# icarus-rev01.net
KiCad netlist of a schematic drawn in EAGLE
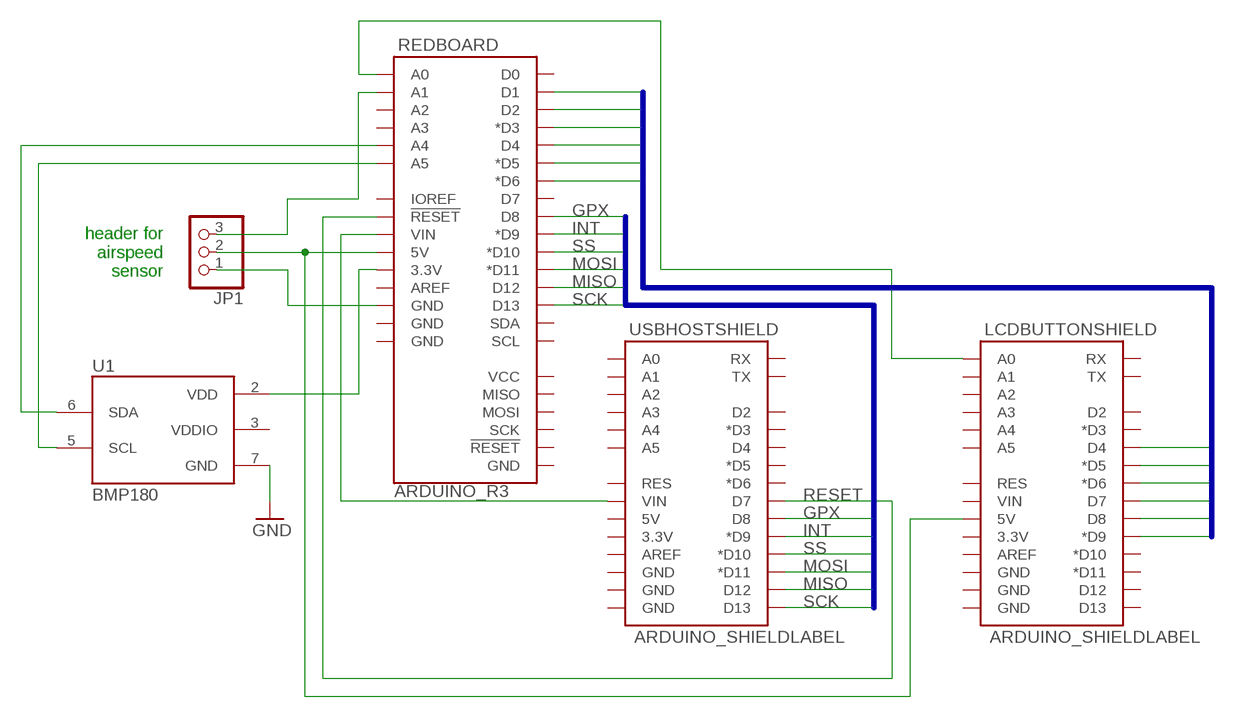
[diagram p0: schematic, sheet 1]

(export (version "E")
  (design (tool "Eeschema 10.0.6"))
  (components
    (comp (ref "JP1")
      (value "PINHD-1X3/90")
      (footprint "eagle-import:1X03_90")
      (libsource (lib "eagle-import") (part "PINHD-1X3/90"))
    )
    (comp (ref "LCDBUTTONSHIELD")
      (value "ARDUINO_SHIELDLABEL")
      (footprint "eagle-import:DUEMILANOVE_SHIELD")
      (libsource (lib "eagle-import") (part "ARDUINO_SHIELDLABEL"))
    )
    (comp (ref "REDBOARD")
      (value "ARDUINO_R3")
      (footprint "eagle-import:ARDUINO_R3")
      (libsource (lib "eagle-import") (part "ARDUINO_R3"))
    )
    (comp (ref "U1")
      (value "BMP180")
      (footprint "eagle-import:BMP180")
      (libsource (lib "eagle-import") (part "BMP180"))
    )
    (comp (ref "USBHOSTSHIELD")
      (value "ARDUINO_SHIELDLABEL")
      (footprint "eagle-import:DUEMILANOVE_SHIELD")
      (libsource (lib "eagle-import") (part "ARDUINO_SHIELDLABEL"))
    )
  )
  (nets
    (net (code "1") (name "/D0") (class "Default")
      (node (ref "LCDBUTTONSHIELD") (pin "D4") (pinfunction "D4_D4") (pintype "bidirectional"))
      (node (ref "REDBOARD") (pin "D4") (pinfunction "D4_D4") (pintype "bidirectional"))
    )
    (net (code "2") (name "/D1") (class "Default")
      (node (ref "LCDBUTTONSHIELD") (pin "D5") (pinfunction "*D5_D5") (pintype "bidirectional"))
      (node (ref "REDBOARD") (pin "D5") (pinfunction "*D5_D5") (pintype "bidirectional"))
    )
    (net (code "3") (name "/D2") (class "Default")
      (node (ref "LCDBUTTONSHIELD") (pin "D6") (pinfunction "*D6_D6") (pintype "bidirectional"))
      (node (ref "REDBOARD") (pin "D6") (pinfunction "*D6_D6") (pintype "bidirectional"))
    )
    (net (code "4") (name "/D3") (class "Default")
      (node (ref "LCDBUTTONSHIELD") (pin "D7") (pinfunction "D7_D7") (pintype "bidirectional"))
      (node (ref "REDBOARD") (pin "D3") (pinfunction "*D3_D3") (pintype "bidirectional"))
    )
    (net (code "5") (name "/D4") (class "Default")
      (node (ref "LCDBUTTONSHIELD") (pin "D8") (pinfunction "D8_D8") (pintype "bidirectional"))
      (node (ref "REDBOARD") (pin "D2") (pinfunction "D2_D2") (pintype "bidirectional"))
    )
    (net (code "6") (name "/GPX") (class "Default")
      (node (ref "REDBOARD") (pin "D8") (pinfunction "D8_D8") (pintype "bidirectional"))
      (node (ref "USBHOSTSHIELD") (pin "D8") (pinfunction "D8_D8") (pintype "bidirectional"))
    )
    (net (code "7") (name "/INT") (class "Default")
      (node (ref "REDBOARD") (pin "D9") (pinfunction "*D9_D9") (pintype "bidirectional"))
      (node (ref "USBHOSTSHIELD") (pin "D9") (pinfunction "*D9_D9") (pintype "bidirectional"))
    )
    (net (code "8") (name "/MISO") (class "Default")
      (node (ref "REDBOARD") (pin "D12") (pinfunction "D12_D12") (pintype "bidirectional"))
      (node (ref "USBHOSTSHIELD") (pin "D12") (pinfunction "D12_D12") (pintype "bidirectional"))
    )
    (net (code "9") (name "/MOSI") (class "Default")
      (node (ref "REDBOARD") (pin "D11") (pinfunction "*D11_D11") (pintype "bidirectional"))
      (node (ref "USBHOSTSHIELD") (pin "D11") (pinfunction "*D11_D11") (pintype "bidirectional"))
    )
    (net (code "10") (name "/RESET") (class "Default")
      (node (ref "REDBOARD") (pin "RESET@1") (pinfunction "~{RESET}_RESET@1") (pintype "bidirectional"))
      (node (ref "USBHOSTSHIELD") (pin "D7") (pinfunction "D7_D7") (pintype "bidirectional"))
    )
    (net (code "11") (name "/SCK") (class "Default")
      (node (ref "REDBOARD") (pin "D13") (pinfunction "D13_D13") (pintype "bidirectional"))
      (node (ref "USBHOSTSHIELD") (pin "D13") (pinfunction "D13_D13") (pintype "bidirectional"))
    )
    (net (code "12") (name "/SS") (class "Default")
      (node (ref "REDBOARD") (pin "D10") (pinfunction "*D10_D10") (pintype "bidirectional"))
      (node (ref "USBHOSTSHIELD") (pin "D10") (pinfunction "*D10_D10") (pintype "bidirectional"))
    )
    (net (code "13") (name "/VDDIO") (class "Default")
      (node (ref "U1") (pin "3") (pinfunction "VDDIO_3") (pintype "power_in"))
    )
    (net (code "14") (name "GND") (class "Default")
      (node (ref "U1") (pin "7") (pinfunction "GND_7") (pintype "power_in"))
    )
    (net (code "15") (name "Net-(JP1-Pad1)") (class "Default")
      (node (ref "JP1") (pin "1") (pinfunction "1_1") (pintype "passive"))
      (node (ref "REDBOARD") (pin "GND@4") (pinfunction "GND_GND@4") (pintype "bidirectional"))
    )
    (net (code "16") (name "Net-(JP1-Pad2)") (class "Default")
      (node (ref "JP1") (pin "2") (pinfunction "2_2") (pintype "passive"))
      (node (ref "LCDBUTTONSHIELD") (pin "5V") (pinfunction "5V_5V") (pintype "bidirectional"))
      (node (ref "REDBOARD") (pin "5V") (pinfunction "5V_5V") (pintype "bidirectional"))
    )
    (net (code "17") (name "Net-(JP1-Pad3)") (class "Default")
      (node (ref "JP1") (pin "3") (pinfunction "3_3") (pintype "passive"))
      (node (ref "REDBOARD") (pin "A1") (pinfunction "A1_A1") (pintype "bidirectional"))
    )
    (net (code "18") (name "Net-(LCDBUTTONSHIELD-PadA0)") (class "Default")
      (node (ref "LCDBUTTONSHIELD") (pin "A0") (pinfunction "A0_A0") (pintype "bidirectional"))
      (node (ref "REDBOARD") (pin "A0") (pinfunction "A0_A0") (pintype "bidirectional"))
    )
    (net (code "19") (name "Net-(REDBOARD-PadVIN)") (class "Default")
      (node (ref "REDBOARD") (pin "VIN") (pinfunction "VIN_VIN") (pintype "bidirectional"))
      (node (ref "USBHOSTSHIELD") (pin "VIN") (pinfunction "VIN_VIN") (pintype "bidirectional"))
    )
    (net (code "20") (name "Net-(U1-SCL)") (class "Default")
      (node (ref "REDBOARD") (pin "A5") (pinfunction "A5_A5") (pintype "bidirectional"))
      (node (ref "U1") (pin "5") (pinfunction "SCL_5") (pintype "input"))
    )
    (net (code "21") (name "Net-(U1-SDA)") (class "Default")
      (node (ref "REDBOARD") (pin "A4") (pinfunction "A4_A4") (pintype "bidirectional"))
      (node (ref "U1") (pin "6") (pinfunction "SDA_6") (pintype "bidirectional"))
    )
    (net (code "22") (name "Net-(U1-VDD)") (class "Default")
      (node (ref "REDBOARD") (pin "3.3V") (pinfunction "3.3V_3.3V") (pintype "bidirectional"))
      (node (ref "U1") (pin "2") (pinfunction "VDD_2") (pintype "power_in"))
    )
    (net (code "23") (name "unconnected-(LCDBUTTONSHIELD-*D3-PadD3)") (class "Default")
      (node (ref "LCDBUTTONSHIELD") (pin "D3") (pinfunction "*D3_D3") (pintype "bidirectional"))
    )
    (net (code "24") (name "unconnected-(LCDBUTTONSHIELD-*D9-PadD9)") (class "Default")
      (node (ref "LCDBUTTONSHIELD") (pin "D9") (pinfunction "*D9_D9") (pintype "bidirectional"))
    )
    (net (code "25") (name "unconnected-(LCDBUTTONSHIELD-*D10-PadD10)") (class "Default")
      (node (ref "LCDBUTTONSHIELD") (pin "D10") (pinfunction "*D10_D10") (pintype "bidirectional"))
    )
    (net (code "26") (name "unconnected-(LCDBUTTONSHIELD-*D11-PadD11)") (class "Default")
      (node (ref "LCDBUTTONSHIELD") (pin "D11") (pinfunction "*D11_D11") (pintype "bidirectional"))
    )
    (net (code "27") (name "unconnected-(LCDBUTTONSHIELD-GND-PadGND@0)") (class "Default")
      (node (ref "LCDBUTTONSHIELD") (pin "GND@0") (pinfunction "GND_GND@0") (pintype "bidirectional"))
    )
    (net (code "28") (name "unconnected-(LCDBUTTONSHIELD-GND-PadGND@1)") (class "Default")
      (node (ref "LCDBUTTONSHIELD") (pin "GND@1") (pinfunction "GND_GND@1") (pintype "bidirectional"))
    )
    (net (code "29") (name "unconnected-(LCDBUTTONSHIELD-GND-PadGND@2)") (class "Default")
      (node (ref "LCDBUTTONSHIELD") (pin "GND@2") (pinfunction "GND_GND@2") (pintype "bidirectional"))
    )
    (net (code "30") (name "unconnected-(LCDBUTTONSHIELD-Pad3.3V)") (class "Default")
      (node (ref "LCDBUTTONSHIELD") (pin "3.3V") (pinfunction "3.3V_3.3V") (pintype "bidirectional"))
    )
    (net (code "31") (name "unconnected-(LCDBUTTONSHIELD-PadA1)") (class "Default")
      (node (ref "LCDBUTTONSHIELD") (pin "A1") (pinfunction "A1_A1") (pintype "bidirectional"))
    )
    (net (code "32") (name "unconnected-(LCDBUTTONSHIELD-PadA2)") (class "Default")
      (node (ref "LCDBUTTONSHIELD") (pin "A2") (pinfunction "A2_A2") (pintype "bidirectional"))
    )
    (net (code "33") (name "unconnected-(LCDBUTTONSHIELD-PadA3)") (class "Default")
      (node (ref "LCDBUTTONSHIELD") (pin "A3") (pinfunction "A3_A3") (pintype "bidirectional"))
    )
    (net (code "34") (name "unconnected-(LCDBUTTONSHIELD-PadA4)") (class "Default")
      (node (ref "LCDBUTTONSHIELD") (pin "A4") (pinfunction "A4_A4") (pintype "bidirectional"))
    )
    (net (code "35") (name "unconnected-(LCDBUTTONSHIELD-PadA5)") (class "Default")
      (node (ref "LCDBUTTONSHIELD") (pin "A5") (pinfunction "A5_A5") (pintype "bidirectional"))
    )
    (net (code "36") (name "unconnected-(LCDBUTTONSHIELD-PadAREF)") (class "Default")
      (node (ref "LCDBUTTONSHIELD") (pin "AREF") (pinfunction "AREF_AREF") (pintype "bidirectional"))
    )
    (net (code "37") (name "unconnected-(LCDBUTTONSHIELD-PadD2)") (class "Default")
      (node (ref "LCDBUTTONSHIELD") (pin "D2") (pinfunction "D2_D2") (pintype "bidirectional"))
    )
    (net (code "38") (name "unconnected-(LCDBUTTONSHIELD-PadD12)") (class "Default")
      (node (ref "LCDBUTTONSHIELD") (pin "D12") (pinfunction "D12_D12") (pintype "bidirectional"))
    )
    (net (code "39") (name "unconnected-(LCDBUTTONSHIELD-PadD13)") (class "Default")
      (node (ref "LCDBUTTONSHIELD") (pin "D13") (pinfunction "D13_D13") (pintype "bidirectional"))
    )
    (net (code "40") (name "unconnected-(LCDBUTTONSHIELD-PadRES)") (class "Default")
      (node (ref "LCDBUTTONSHIELD") (pin "RES") (pinfunction "RES_RES") (pintype "bidirectional"))
    )
    (net (code "41") (name "unconnected-(LCDBUTTONSHIELD-PadRX)") (class "Default")
      (node (ref "LCDBUTTONSHIELD") (pin "RX") (pinfunction "RX_RX") (pintype "bidirectional"))
    )
    (net (code "42") (name "unconnected-(LCDBUTTONSHIELD-PadTX)") (class "Default")
      (node (ref "LCDBUTTONSHIELD") (pin "TX") (pinfunction "TX_TX") (pintype "bidirectional"))
    )
    (net (code "43") (name "unconnected-(LCDBUTTONSHIELD-PadVIN)") (class "Default")
      (node (ref "LCDBUTTONSHIELD") (pin "VIN") (pinfunction "VIN_VIN") (pintype "bidirectional"))
    )
    (net (code "44") (name "unconnected-(REDBOARD-GND-PadGND@1)") (class "Default")
      (node (ref "REDBOARD") (pin "GND@1") (pinfunction "GND_GND@1") (pintype "bidirectional"))
    )
    (net (code "45") (name "unconnected-(REDBOARD-GND-PadGND@2)") (class "Default")
      (node (ref "REDBOARD") (pin "GND@2") (pinfunction "GND_GND@2") (pintype "bidirectional"))
    )
    (net (code "46") (name "unconnected-(REDBOARD-GND-PadGND@3)") (class "Default")
      (node (ref "REDBOARD") (pin "GND@3") (pinfunction "GND_GND@3") (pintype "bidirectional"))
    )
    (net (code "47") (name "unconnected-(REDBOARD-PadA2)") (class "Default")
      (node (ref "REDBOARD") (pin "A2") (pinfunction "A2_A2") (pintype "bidirectional"))
    )
    (net (code "48") (name "unconnected-(REDBOARD-PadA3)") (class "Default")
      (node (ref "REDBOARD") (pin "A3") (pinfunction "A3_A3") (pintype "bidirectional"))
    )
    (net (code "49") (name "unconnected-(REDBOARD-PadAREF)") (class "Default")
      (node (ref "REDBOARD") (pin "AREF") (pinfunction "AREF_AREF") (pintype "bidirectional"))
    )
    (net (code "50") (name "unconnected-(REDBOARD-PadD0)") (class "Default")
      (node (ref "REDBOARD") (pin "D0") (pinfunction "D0_D0") (pintype "bidirectional"))
    )
    (net (code "51") (name "unconnected-(REDBOARD-PadD1)") (class "Default")
      (node (ref "REDBOARD") (pin "D1") (pinfunction "D1_D1") (pintype "bidirectional"))
    )
    (net (code "52") (name "unconnected-(REDBOARD-PadD7)") (class "Default")
      (node (ref "REDBOARD") (pin "D7") (pinfunction "D7_D7") (pintype "bidirectional"))
    )
    (net (code "53") (name "unconnected-(REDBOARD-PadIOREF)") (class "Default")
      (node (ref "REDBOARD") (pin "IOREF") (pinfunction "IOREF_IOREF") (pintype "bidirectional"))
    )
    (net (code "54") (name "unconnected-(REDBOARD-PadMISO)") (class "Default")
      (node (ref "REDBOARD") (pin "MISO") (pinfunction "MISO_MISO") (pintype "bidirectional"))
    )
    (net (code "55") (name "unconnected-(REDBOARD-PadMOSI)") (class "Default")
      (node (ref "REDBOARD") (pin "MOSI") (pinfunction "MOSI_MOSI") (pintype "bidirectional"))
    )
    (net (code "56") (name "unconnected-(REDBOARD-PadSCK)") (class "Default")
      (node (ref "REDBOARD") (pin "SCK") (pinfunction "SCK_SCK") (pintype "bidirectional"))
    )
    (net (code "57") (name "unconnected-(REDBOARD-PadSCL)") (class "Default")
      (node (ref "REDBOARD") (pin "SCL") (pinfunction "SCL_SCL") (pintype "bidirectional"))
    )
    (net (code "58") (name "unconnected-(REDBOARD-PadSDA)") (class "Default")
      (node (ref "REDBOARD") (pin "SDA") (pinfunction "SDA_SDA") (pintype "bidirectional"))
    )
    (net (code "59") (name "unconnected-(REDBOARD-PadVCC)") (class "Default")
      (node (ref "REDBOARD") (pin "VCC") (pinfunction "VCC_VCC") (pintype "bidirectional"))
    )
    (net (code "60") (name "unconnected-(REDBOARD-~{RESET}-PadRESET@2)") (class "Default")
      (node (ref "REDBOARD") (pin "RESET@2") (pinfunction "~{RESET}_RESET@2") (pintype "bidirectional"))
    )
    (net (code "61") (name "unconnected-(USBHOSTSHIELD-*D3-PadD3)") (class "Default")
      (node (ref "USBHOSTSHIELD") (pin "D3") (pinfunction "*D3_D3") (pintype "bidirectional"))
    )
    (net (code "62") (name "unconnected-(USBHOSTSHIELD-*D5-PadD5)") (class "Default")
      (node (ref "USBHOSTSHIELD") (pin "D5") (pinfunction "*D5_D5") (pintype "bidirectional"))
    )
    (net (code "63") (name "unconnected-(USBHOSTSHIELD-*D6-PadD6)") (class "Default")
      (node (ref "USBHOSTSHIELD") (pin "D6") (pinfunction "*D6_D6") (pintype "bidirectional"))
    )
    (net (code "64") (name "unconnected-(USBHOSTSHIELD-GND-PadGND@0)") (class "Default")
      (node (ref "USBHOSTSHIELD") (pin "GND@0") (pinfunction "GND_GND@0") (pintype "bidirectional"))
    )
    (net (code "65") (name "unconnected-(USBHOSTSHIELD-GND-PadGND@1)") (class "Default")
      (node (ref "USBHOSTSHIELD") (pin "GND@1") (pinfunction "GND_GND@1") (pintype "bidirectional"))
    )
    (net (code "66") (name "unconnected-(USBHOSTSHIELD-GND-PadGND@2)") (class "Default")
      (node (ref "USBHOSTSHIELD") (pin "GND@2") (pinfunction "GND_GND@2") (pintype "bidirectional"))
    )
    (net (code "67") (name "unconnected-(USBHOSTSHIELD-Pad3.3V)") (class "Default")
      (node (ref "USBHOSTSHIELD") (pin "3.3V") (pinfunction "3.3V_3.3V") (pintype "bidirectional"))
    )
    (net (code "68") (name "unconnected-(USBHOSTSHIELD-Pad5V)") (class "Default")
      (node (ref "USBHOSTSHIELD") (pin "5V") (pinfunction "5V_5V") (pintype "bidirectional"))
    )
    (net (code "69") (name "unconnected-(USBHOSTSHIELD-PadA0)") (class "Default")
      (node (ref "USBHOSTSHIELD") (pin "A0") (pinfunction "A0_A0") (pintype "bidirectional"))
    )
    (net (code "70") (name "unconnected-(USBHOSTSHIELD-PadA1)") (class "Default")
      (node (ref "USBHOSTSHIELD") (pin "A1") (pinfunction "A1_A1") (pintype "bidirectional"))
    )
    (net (code "71") (name "unconnected-(USBHOSTSHIELD-PadA2)") (class "Default")
      (node (ref "USBHOSTSHIELD") (pin "A2") (pinfunction "A2_A2") (pintype "bidirectional"))
    )
    (net (code "72") (name "unconnected-(USBHOSTSHIELD-PadA3)") (class "Default")
      (node (ref "USBHOSTSHIELD") (pin "A3") (pinfunction "A3_A3") (pintype "bidirectional"))
    )
    (net (code "73") (name "unconnected-(USBHOSTSHIELD-PadA4)") (class "Default")
      (node (ref "USBHOSTSHIELD") (pin "A4") (pinfunction "A4_A4") (pintype "bidirectional"))
    )
    (net (code "74") (name "unconnected-(USBHOSTSHIELD-PadA5)") (class "Default")
      (node (ref "USBHOSTSHIELD") (pin "A5") (pinfunction "A5_A5") (pintype "bidirectional"))
    )
    (net (code "75") (name "unconnected-(USBHOSTSHIELD-PadAREF)") (class "Default")
      (node (ref "USBHOSTSHIELD") (pin "AREF") (pinfunction "AREF_AREF") (pintype "bidirectional"))
    )
    (net (code "76") (name "unconnected-(USBHOSTSHIELD-PadD2)") (class "Default")
      (node (ref "USBHOSTSHIELD") (pin "D2") (pinfunction "D2_D2") (pintype "bidirectional"))
    )
    (net (code "77") (name "unconnected-(USBHOSTSHIELD-PadD4)") (class "Default")
      (node (ref "USBHOSTSHIELD") (pin "D4") (pinfunction "D4_D4") (pintype "bidirectional"))
    )
    (net (code "78") (name "unconnected-(USBHOSTSHIELD-PadRES)") (class "Default")
      (node (ref "USBHOSTSHIELD") (pin "RES") (pinfunction "RES_RES") (pintype "bidirectional"))
    )
    (net (code "79") (name "unconnected-(USBHOSTSHIELD-PadRX)") (class "Default")
      (node (ref "USBHOSTSHIELD") (pin "RX") (pinfunction "RX_RX") (pintype "bidirectional"))
    )
    (net (code "80") (name "unconnected-(USBHOSTSHIELD-PadTX)") (class "Default")
      (node (ref "USBHOSTSHIELD") (pin "TX") (pinfunction "TX_TX") (pintype "bidirectional"))
    )
  )
)
